# esp-core.net
KiCad netlist of a schematic drawn in EAGLE
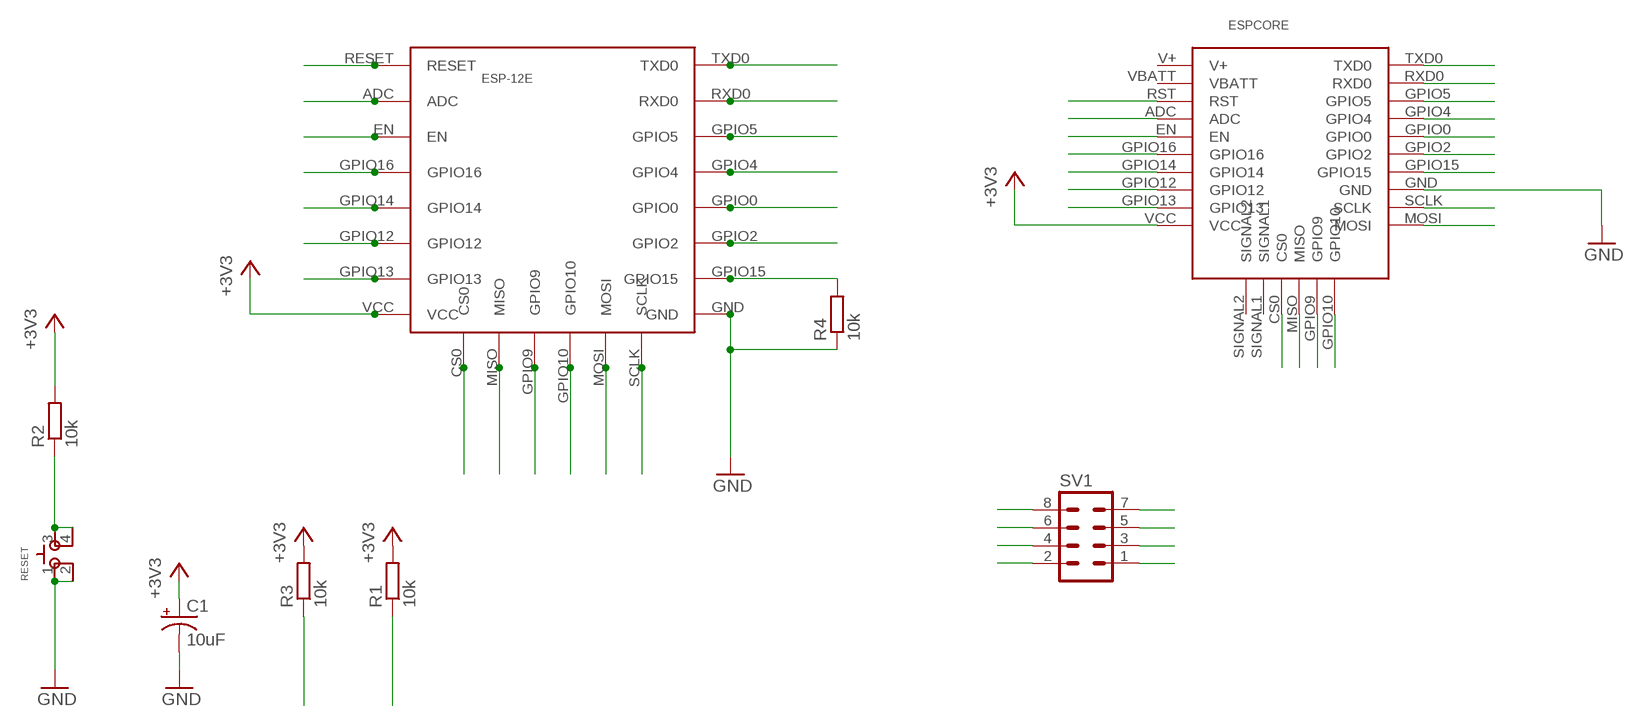
[diagram p0: schematic, sheet 1]

(export (version "E")
  (design (tool "Eeschema 10.0.6"))
  (components
    (comp (ref "C1")
      (value "10uF")
      (footprint "eagle-import:EIA3216")
      (libsource (lib "eagle-import") (part "10UF-16V-10%(TANT)"))
    )
    (comp (ref "ESP-12E")
      (value "ESP-12E")
      (footprint "eagle-import:ESP-12E")
      (libsource (lib "eagle-import") (part "ESP-12E"))
    )
    (comp (ref "ESPCORE")
      (value "ESP-BOARD")
      (footprint "eagle-import:ESP-BOARD")
      (libsource (lib "eagle-import") (part "ESP-BOARD"))
    )
    (comp (ref "R1")
      (value "10k")
      (footprint "eagle-import:R1206")
      (libsource (lib "eagle-import") (part "RESISTOR-1206"))
    )
    (comp (ref "R2")
      (value "10k")
      (footprint "eagle-import:R1206")
      (libsource (lib "eagle-import") (part "RESISTOR-1206"))
    )
    (comp (ref "R3")
      (value "10k")
      (footprint "eagle-import:R1206")
      (libsource (lib "eagle-import") (part "RESISTOR-1206"))
    )
    (comp (ref "R4")
      (value "10k")
      (footprint "eagle-import:R1206")
      (libsource (lib "eagle-import") (part "RESISTOR-1206"))
    )
    (comp (ref "RESET")
      (value "SKSCLDE010")
      (footprint "eagle-import:SKSCLDE010")
      (libsource (lib "eagle-import") (part "SKSCLDE010"))
    )
    (comp (ref "SV1")
      (value "MA04-2")
      (footprint "eagle-import:MA04-2")
      (libsource (lib "eagle-import") (part "MA04-2"))
    )
  )
  (nets
    (net (code "1") (name "+3V3") (class "Default")
      (node (ref "C1") (pin "A") (pinfunction "+_A") (pintype "passive"))
      (node (ref "ESP-12E") (pin "VCC") (pinfunction "VCC_VCC") (pintype "power_in"))
      (node (ref "ESPCORE") (pin "VCC") (pinfunction "VCC_VCC") (pintype "power_in"))
      (node (ref "R1") (pin "2") (pinfunction "2_2") (pintype "passive"))
      (node (ref "R2") (pin "2") (pinfunction "2_2") (pintype "passive"))
      (node (ref "R3") (pin "2") (pinfunction "2_2") (pintype "passive"))
      (node (ref "SV1") (pin "7") (pinfunction "7_7") (pintype "passive"))
    )
    (net (code "2") (name "/ADC") (class "Default")
      (node (ref "ESP-12E") (pin "ADC") (pinfunction "ADC_ADC") (pintype "bidirectional"))
      (node (ref "ESPCORE") (pin "ADC") (pinfunction "ADC_ADC") (pintype "bidirectional"))
    )
    (net (code "3") (name "/CS0") (class "Default")
      (node (ref "ESP-12E") (pin "CS0") (pinfunction "CS0_CS0") (pintype "bidirectional"))
      (node (ref "ESPCORE") (pin "CS0") (pinfunction "CS0_CS0") (pintype "bidirectional"))
    )
    (net (code "4") (name "/EN") (class "Default")
      (node (ref "ESP-12E") (pin "EN") (pinfunction "EN_EN") (pintype "bidirectional"))
      (node (ref "ESPCORE") (pin "EN") (pinfunction "EN_EN") (pintype "bidirectional"))
      (node (ref "R1") (pin "1") (pinfunction "1_1") (pintype "passive"))
      (node (ref "SV1") (pin "3") (pinfunction "3_3") (pintype "passive"))
    )
    (net (code "5") (name "/GPIO0") (class "Default")
      (node (ref "ESP-12E") (pin "GPIO0") (pinfunction "GPIO0_GPIO0") (pintype "bidirectional"))
      (node (ref "ESPCORE") (pin "GPIO0") (pinfunction "GPIO0_GPIO0") (pintype "bidirectional"))
      (node (ref "R3") (pin "1") (pinfunction "1_1") (pintype "passive"))
      (node (ref "SV1") (pin "6") (pinfunction "6_6") (pintype "passive"))
    )
    (net (code "6") (name "/GPIO2") (class "Default")
      (node (ref "ESP-12E") (pin "GPIO2") (pinfunction "GPIO2_GPIO2") (pintype "bidirectional"))
      (node (ref "ESPCORE") (pin "GPIO2") (pinfunction "GPIO2_GPIO2") (pintype "bidirectional"))
      (node (ref "SV1") (pin "4") (pinfunction "4_4") (pintype "passive"))
    )
    (net (code "7") (name "/GPIO4") (class "Default")
      (node (ref "ESP-12E") (pin "GPIO4") (pinfunction "GPIO4_GPIO4") (pintype "bidirectional"))
      (node (ref "ESPCORE") (pin "GPIO4") (pinfunction "GPIO4_GPIO4") (pintype "bidirectional"))
    )
    (net (code "8") (name "/GPIO5") (class "Default")
      (node (ref "ESP-12E") (pin "GPIO5") (pinfunction "GPIO5_GPIO5") (pintype "bidirectional"))
      (node (ref "ESPCORE") (pin "GPIO5") (pinfunction "GPIO5_GPIO5") (pintype "bidirectional"))
    )
    (net (code "9") (name "/GPIO9") (class "Default")
      (node (ref "ESP-12E") (pin "GPIO9") (pinfunction "GPIO9_GPIO9") (pintype "bidirectional"))
      (node (ref "ESPCORE") (pin "GPIO9") (pinfunction "GPIO9_GPIO9") (pintype "bidirectional"))
    )
    (net (code "10") (name "/GPIO10") (class "Default")
      (node (ref "ESP-12E") (pin "GPIO10") (pinfunction "GPIO10_GPIO10") (pintype "bidirectional"))
      (node (ref "ESPCORE") (pin "GPIO10") (pinfunction "GPIO10_GPIO10") (pintype "bidirectional"))
    )
    (net (code "11") (name "/GPIO12") (class "Default")
      (node (ref "ESP-12E") (pin "GPIO12") (pinfunction "GPIO12_GPIO12") (pintype "bidirectional"))
      (node (ref "ESPCORE") (pin "GPIO12") (pinfunction "GPIO12_GPIO12") (pintype "bidirectional"))
    )
    (net (code "12") (name "/GPIO13") (class "Default")
      (node (ref "ESP-12E") (pin "GPIO13") (pinfunction "GPIO13_GPIO13") (pintype "bidirectional"))
      (node (ref "ESPCORE") (pin "GPIO13") (pinfunction "GPIO13_GPIO13") (pintype "bidirectional"))
    )
    (net (code "13") (name "/GPIO14") (class "Default")
      (node (ref "ESP-12E") (pin "GPIO14") (pinfunction "GPIO14_GPIO14") (pintype "bidirectional"))
      (node (ref "ESPCORE") (pin "GPIO14") (pinfunction "GPIO14_GPIO14") (pintype "bidirectional"))
    )
    (net (code "14") (name "/GPIO15") (class "Default")
      (node (ref "ESP-12E") (pin "GPIO15") (pinfunction "GPIO15_GPIO15") (pintype "bidirectional"))
      (node (ref "ESPCORE") (pin "GPIO15") (pinfunction "GPIO15_GPIO15") (pintype "bidirectional"))
      (node (ref "R4") (pin "2") (pinfunction "2_2") (pintype "passive"))
    )
    (net (code "15") (name "/GPIO16") (class "Default")
      (node (ref "ESP-12E") (pin "GPIO16") (pinfunction "GPIO16_GPIO16") (pintype "bidirectional"))
      (node (ref "ESPCORE") (pin "GPIO16") (pinfunction "GPIO16_GPIO16") (pintype "bidirectional"))
    )
    (net (code "16") (name "/MISO") (class "Default")
      (node (ref "ESP-12E") (pin "MISO") (pinfunction "MISO_MISO") (pintype "bidirectional"))
      (node (ref "ESPCORE") (pin "MISO") (pinfunction "MISO_MISO") (pintype "bidirectional"))
    )
    (net (code "17") (name "/MOSI") (class "Default")
      (node (ref "ESP-12E") (pin "MOSI") (pinfunction "MOSI_MOSI") (pintype "bidirectional"))
      (node (ref "ESPCORE") (pin "MOSI") (pinfunction "MOSI_MOSI") (pintype "bidirectional"))
    )
    (net (code "18") (name "/RESET") (class "Default")
      (node (ref "ESP-12E") (pin "RESET") (pinfunction "RESET_RESET") (pintype "bidirectional"))
      (node (ref "ESPCORE") (pin "RST") (pinfunction "RST_RST") (pintype "bidirectional"))
      (node (ref "R2") (pin "1") (pinfunction "1_1") (pintype "passive"))
      (node (ref "RESET") (pin "3") (pinfunction "4_3") (pintype "bidirectional"))
      (node (ref "RESET") (pin "4") (pinfunction "3_4") (pintype "bidirectional"))
      (node (ref "SV1") (pin "5") (pinfunction "5_5") (pintype "passive"))
    )
    (net (code "19") (name "/RXD0") (class "Default")
      (node (ref "ESP-12E") (pin "RXD0") (pinfunction "RXD0_RXD0") (pintype "bidirectional"))
      (node (ref "ESPCORE") (pin "RXD0") (pinfunction "RXD0_RXD0") (pintype "bidirectional"))
      (node (ref "SV1") (pin "8") (pinfunction "8_8") (pintype "passive"))
    )
    (net (code "20") (name "/SCLK") (class "Default")
      (node (ref "ESP-12E") (pin "SCLK") (pinfunction "SCLK_SCLK") (pintype "bidirectional"))
      (node (ref "ESPCORE") (pin "SCLK") (pinfunction "SCLK_SCLK") (pintype "bidirectional"))
    )
    (net (code "21") (name "/TXD0") (class "Default")
      (node (ref "ESP-12E") (pin "TXD0") (pinfunction "TXD0_TXD0") (pintype "bidirectional"))
      (node (ref "ESPCORE") (pin "TXD0") (pinfunction "TXD0_TXD0") (pintype "bidirectional"))
      (node (ref "SV1") (pin "1") (pinfunction "1_1") (pintype "passive"))
    )
    (net (code "22") (name "/V+") (class "Default")
      (node (ref "ESPCORE") (pin "V+") (pinfunction "V+_V+") (pintype "power_in"))
    )
    (net (code "23") (name "/VBATT") (class "Default")
      (node (ref "ESPCORE") (pin "VBATT") (pinfunction "VBATT_VBATT") (pintype "power_in"))
    )
    (net (code "24") (name "GND") (class "Default")
      (node (ref "C1") (pin "C") (pinfunction "-_C") (pintype "passive"))
      (node (ref "ESP-12E") (pin "GND") (pinfunction "GND_GND") (pintype "power_in"))
      (node (ref "ESPCORE") (pin "GND") (pinfunction "GND_GND") (pintype "power_in"))
      (node (ref "R4") (pin "1") (pinfunction "1_1") (pintype "passive"))
      (node (ref "RESET") (pin "1") (pinfunction "1_1") (pintype "bidirectional"))
      (node (ref "RESET") (pin "2") (pinfunction "2_2") (pintype "bidirectional"))
      (node (ref "SV1") (pin "2") (pinfunction "2_2") (pintype "passive"))
    )
    (net (code "25") (name "unconnected-(ESPCORE-PadSIGNAL1)") (class "Default")
      (node (ref "ESPCORE") (pin "SIGNAL1") (pinfunction "SIGNAL1_SIGNAL1") (pintype "bidirectional"))
    )
    (net (code "26") (name "unconnected-(ESPCORE-PadSIGNAL2)") (class "Default")
      (node (ref "ESPCORE") (pin "SIGNAL2") (pinfunction "SIGNAL2_SIGNAL2") (pintype "bidirectional"))
    )
  )
)
